# Powered_USB_Blaster.net
KiCad netlist of a schematic drawn in EAGLE
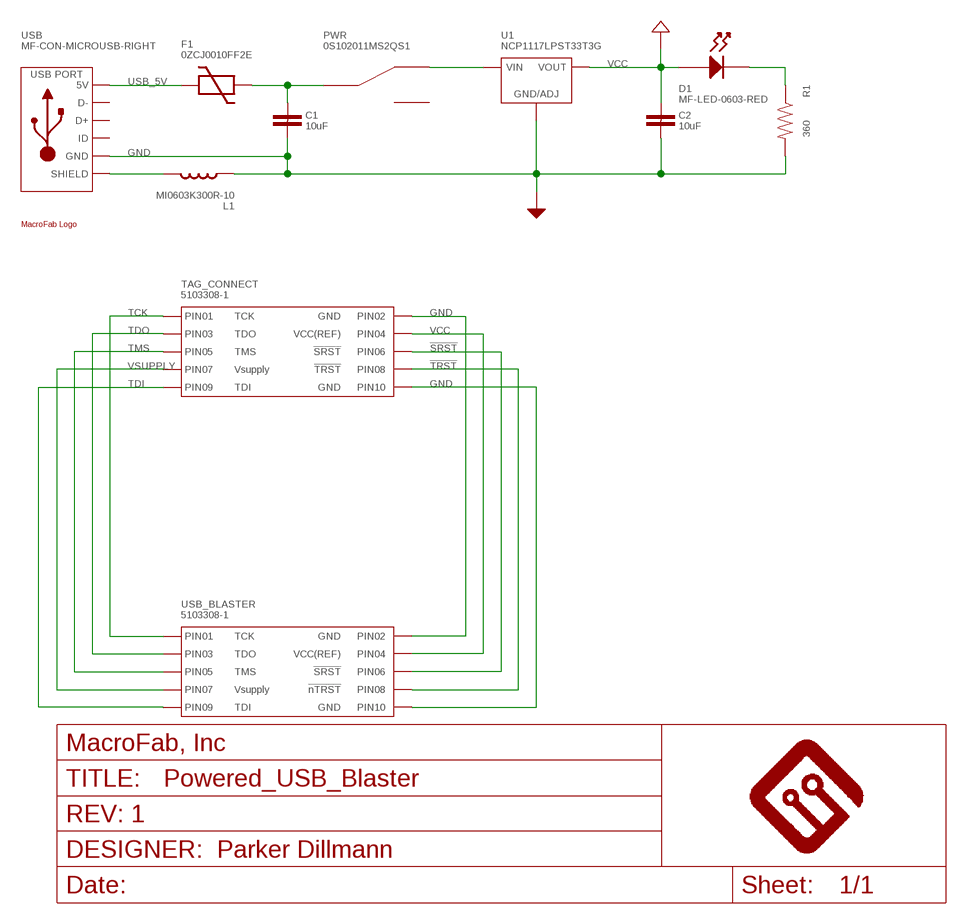
[diagram p0: schematic, sheet 1]

(export (version "E")
  (design (tool "Eeschema 10.0.6"))
  (components
    (comp (ref "C1")
      (value "10uF")
      (footprint "eagle-import:1206")
      (libsource (lib "eagle-import") (part "CAPACITOR_NON_POLAR_1206"))
    )
    (comp (ref "C2")
      (value "10uF")
      (footprint "eagle-import:1206")
      (libsource (lib "eagle-import") (part "CAPACITOR_NON_POLAR_1206"))
    )
    (comp (ref "D1")
      (value "MF-LED-0603-RED")
      (footprint "eagle-import:LED0805")
      (libsource (lib "eagle-import") (part "LED_SINGLE_0805"))
    )
    (comp (ref "F1")
      (value "0ZCJ0010FF2E")
      (footprint "eagle-import:1206")
      (libsource (lib "eagle-import") (part "PTC_FUSE_1206"))
    )
    (comp (ref "FRAME1")
      (value "MF_FRAMEDEFAULT")
      (footprint "eagle-import:MF_FRAME_DEFAULT")
      (fields (field (name "DNAME") "Parker Dillmann") (field (name "REVNUM") "REV: 1"))
      (libsource (lib "eagle-import") (part "MF_FRAMEDEFAULT"))
    )
    (comp (ref "L1")
      (value "MI0603K300R-10")
      (footprint "eagle-import:L0603")
      (libsource (lib "eagle-import") (part "INDUCTOR_0603"))
    )
    (comp (ref "PWR")
      (value "0S102011MS2QS1")
      (footprint "eagle-import:0S102011MS2QS1")
      (libsource (lib "eagle-import") (part "SPDT_0S102011MS2QS1"))
    )
    (comp (ref "R1")
      (value "360")
      (footprint "eagle-import:R0805")
      (libsource (lib "eagle-import") (part "RESISTOR_0805"))
    )
    (comp (ref "TAG_CONNECT")
      (value "5103308-1")
      (footprint "eagle-import:5103308-1")
      (fields
        (field (name "LABEL01") "TCK")
        (field (name "LABEL02") "GND")
        (field (name "LABEL03") "TDO")
        (field (name "LABEL04") "VCC(REF)")
        (field (name "LABEL05") "TMS")
        (field (name "LABEL06") "!SRST")
        (field (name "LABEL07") "Vsupply")
        (field (name "LABEL08") "!TRST")
        (field (name "LABEL09") "TDI")
        (field (name "LABEL10") "GND")
      )
      (libsource (lib "eagle-import") (part "CON_02X05_5103308-1"))
    )
    (comp (ref "U$3")
      (value "MF_LOGOLOGO_MEDIUM")
      (footprint "eagle-import:MF_LOGO_MEDIUM")
      (libsource (lib "eagle-import") (part "MF_LOGOLOGO_MEDIUM"))
    )
    (comp (ref "U1")
      (value "NCP1117LPST33T3G")
      (footprint "eagle-import:SOT-223-3")
      (libsource (lib "eagle-import") (part "NCP1117LPST33T3G"))
    )
    (comp (ref "USB")
      (value "MF-CON-MICROUSB-RIGHT")
      (footprint "eagle-import:MICROUSB-RIGHT")
      (libsource (lib "eagle-import") (part "USB_MICRO_RIGHT"))
    )
    (comp (ref "USB_BLASTER")
      (value "5103308-1")
      (footprint "eagle-import:5103308-1")
      (fields
        (field (name "LABEL01") "TCK")
        (field (name "LABEL02") "GND")
        (field (name "LABEL03") "TDO")
        (field (name "LABEL04") "VCC(REF)")
        (field (name "LABEL05") "TMS")
        (field (name "LABEL06") "!SRST")
        (field (name "LABEL07") "Vsupply")
        (field (name "LABEL08") "!nTRST")
        (field (name "LABEL09") "TDI")
        (field (name "LABEL10") "GND")
      )
      (libsource (lib "eagle-import") (part "CON_02X05_5103308-1"))
    )
  )
  (nets
    (net (code "1") (name "/TCK") (class "Default")
      (node (ref "TAG_CONNECT") (pin "1") (pinfunction "PIN1_1") (pintype "bidirectional"))
      (node (ref "USB_BLASTER") (pin "1") (pinfunction "PIN1_1") (pintype "bidirectional"))
    )
    (net (code "2") (name "/TDI") (class "Default")
      (node (ref "TAG_CONNECT") (pin "9") (pinfunction "PIN9_9") (pintype "bidirectional"))
      (node (ref "USB_BLASTER") (pin "9") (pinfunction "PIN9_9") (pintype "bidirectional"))
    )
    (net (code "3") (name "/TDO") (class "Default")
      (node (ref "TAG_CONNECT") (pin "3") (pinfunction "PIN3_3") (pintype "bidirectional"))
      (node (ref "USB_BLASTER") (pin "3") (pinfunction "PIN3_3") (pintype "bidirectional"))
    )
    (net (code "4") (name "/TMS") (class "Default")
      (node (ref "TAG_CONNECT") (pin "5") (pinfunction "PIN5_5") (pintype "bidirectional"))
      (node (ref "USB_BLASTER") (pin "5") (pinfunction "PIN5_5") (pintype "bidirectional"))
    )
    (net (code "5") (name "/USB_5V") (class "Default")
      (node (ref "F1") (pin "1") (pinfunction "P$1_1") (pintype "bidirectional"))
      (node (ref "USB") (pin "1") (pinfunction "5V_1") (pintype "power_in"))
    )
    (net (code "6") (name "/VSUPPLY") (class "Default")
      (node (ref "TAG_CONNECT") (pin "7") (pinfunction "PIN7_7") (pintype "bidirectional"))
      (node (ref "USB_BLASTER") (pin "7") (pinfunction "PIN7_7") (pintype "bidirectional"))
    )
    (net (code "7") (name "/~{SRST}") (class "Default")
      (node (ref "TAG_CONNECT") (pin "6") (pinfunction "PIN6_6") (pintype "bidirectional"))
      (node (ref "USB_BLASTER") (pin "6") (pinfunction "PIN6_6") (pintype "bidirectional"))
    )
    (net (code "8") (name "/~{TRST}") (class "Default")
      (node (ref "TAG_CONNECT") (pin "8") (pinfunction "PIN8_8") (pintype "bidirectional"))
      (node (ref "USB_BLASTER") (pin "8") (pinfunction "PIN8_8") (pintype "bidirectional"))
    )
    (net (code "9") (name "GND_RAIL") (class "Default")
      (node (ref "C1") (pin "2") (pinfunction "2_2") (pintype "passive"))
      (node (ref "C2") (pin "2") (pinfunction "2_2") (pintype "passive"))
      (node (ref "L1") (pin "P$1") (pinfunction "P$1_P$1") (pintype "passive"))
      (node (ref "R1") (pin "P$2") (pinfunction "P$2_P$2") (pintype "passive"))
      (node (ref "TAG_CONNECT") (pin "10") (pinfunction "PIN10_10") (pintype "bidirectional"))
      (node (ref "TAG_CONNECT") (pin "2") (pinfunction "PIN2_2") (pintype "bidirectional"))
      (node (ref "U1") (pin "P$2") (pinfunction "GND/ADJ_P$2") (pintype "bidirectional"))
      (node (ref "USB") (pin "5") (pinfunction "GND_5") (pintype "power_in"))
      (node (ref "USB_BLASTER") (pin "10") (pinfunction "PIN10_10") (pintype "bidirectional"))
      (node (ref "USB_BLASTER") (pin "2") (pinfunction "PIN2_2") (pintype "bidirectional"))
    )
    (net (code "10") (name "Net-(D1-PadCATHODE)") (class "Default")
      (node (ref "D1") (pin "CATHODE") (pinfunction "CATHODE_CATHODE") (pintype "power_in"))
      (node (ref "R1") (pin "P$1") (pinfunction "P$1_P$1") (pintype "passive"))
    )
    (net (code "11") (name "Net-(F1-P$2)") (class "Default")
      (node (ref "C1") (pin "1") (pinfunction "1_1") (pintype "passive"))
      (node (ref "F1") (pin "2") (pinfunction "P$2_2") (pintype "bidirectional"))
      (node (ref "PWR") (pin "2") (pinfunction "C_2") (pintype "bidirectional"))
    )
    (net (code "12") (name "Net-(L1-PadP$2)") (class "Default")
      (node (ref "L1") (pin "P$2") (pinfunction "P$2_P$2") (pintype "passive"))
      (node (ref "USB") (pin "S1") (pinfunction "SLD_S1") (pintype "power_in"))
      (node (ref "USB") (pin "S2") (pinfunction "SLD_S2") (pintype "power_in"))
      (node (ref "USB") (pin "S3") (pinfunction "SLD_S3") (pintype "power_in"))
      (node (ref "USB") (pin "S4") (pinfunction "SLD_S4") (pintype "power_in"))
      (node (ref "USB") (pin "S5") (pinfunction "SLD_S5") (pintype "power_in"))
      (node (ref "USB") (pin "S6") (pinfunction "SLD_S6") (pintype "power_in"))
    )
    (net (code "13") (name "Net-(U1-VIN)") (class "Default")
      (node (ref "PWR") (pin "1") (pinfunction "1_1") (pintype "bidirectional"))
      (node (ref "U1") (pin "P$4") (pinfunction "VIN_P$4") (pintype "bidirectional"))
    )
    (net (code "14") (name "POWER_RAIL") (class "Default")
      (node (ref "C2") (pin "1") (pinfunction "1_1") (pintype "passive"))
      (node (ref "D1") (pin "ANODE") (pinfunction "ANODE_ANODE") (pintype "power_in"))
      (node (ref "TAG_CONNECT") (pin "4") (pinfunction "PIN4_4") (pintype "bidirectional"))
      (node (ref "U1") (pin "P$1") (pinfunction "VOUT_P$1") (pintype "bidirectional"))
      (node (ref "U1") (pin "P$3") (pinfunction "VOUT_P$3") (pintype "bidirectional"))
      (node (ref "USB_BLASTER") (pin "4") (pinfunction "PIN4_4") (pintype "bidirectional"))
    )
    (net (code "15") (name "unconnected-(PWR-2-Pad3)") (class "Default")
      (node (ref "PWR") (pin "3") (pinfunction "2_3") (pintype "bidirectional"))
    )
    (net (code "16") (name "unconnected-(USB-D+-Pad3)") (class "Default")
      (node (ref "USB") (pin "3") (pinfunction "D+_3") (pintype "bidirectional"))
    )
    (net (code "17") (name "unconnected-(USB-D--Pad2)") (class "Default")
      (node (ref "USB") (pin "2") (pinfunction "D-_2") (pintype "bidirectional"))
    )
    (net (code "18") (name "unconnected-(USB-ID-Pad4)") (class "Default")
      (node (ref "USB") (pin "4") (pinfunction "ID_4") (pintype "bidirectional"))
    )
  )
)
